# Back.net
KiCad netlist of a schematic drawn in Altium Designer
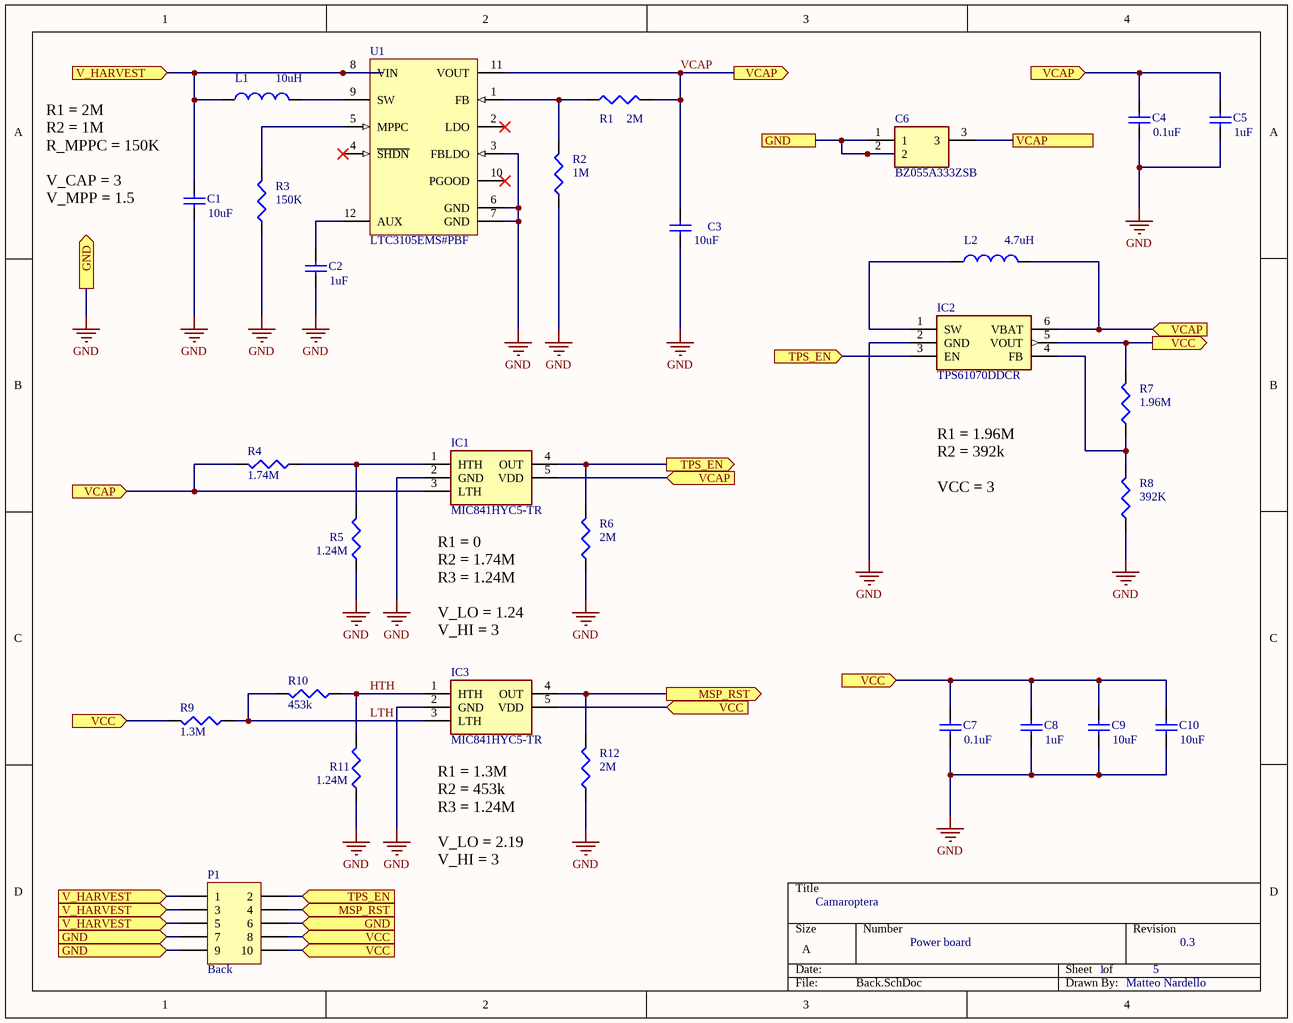
[diagram p0: Back.SchDoc]

(export (version "E")
  (design (tool "Eeschema 10.0.6"))
  (components
    (comp (ref "C1")
      (value "10uF")
      (footprint "1608[0603]")
      (description "CAP CER 6.3V X5R/X7R 0603")
      (fields (field (name "Comment") "Cap") (field (name "PUBLISHER") "Altium Limited"))
      (libsource (lib "Miscellaneous Devices") (part "Cap"))
    )
    (comp (ref "C2")
      (value "1uF")
      (footprint "1608[0603]")
      (description "CAP CER 6.3V X5R/X7R 0603")
      (fields (field (name "Comment") "Cap") (field (name "PUBLISHER") "Altium Limited"))
      (libsource (lib "Miscellaneous Devices") (part "Cap"))
    )
    (comp (ref "C3")
      (value "10uF")
      (footprint "1608[0603]")
      (description "CAP CER 6.3V X5R/X7R 0603")
      (fields (field (name "Comment") "Cap") (field (name "PUBLISHER") "Altium Limited"))
      (libsource (lib "Miscellaneous Devices") (part "Cap"))
    )
    (comp (ref "C4")
      (value "0.1uF")
      (footprint "1608[0603]")
      (description "CAP CER 6.3V X5R/X7R 0603")
      (fields (field (name "Comment") "Cap") (field (name "PUBLISHER") "Altium Limited"))
      (libsource (lib "Miscellaneous Devices") (part "Cap"))
    )
    (comp (ref "C5")
      (value "1uF")
      (footprint "1608[0603]")
      (description "CAP CER 6.3V X5R/X7R 0603")
      (fields (field (name "Comment") "Cap") (field (name "PUBLISHER") "Altium Limited"))
      (libsource (lib "Miscellaneous Devices") (part "Cap"))
    )
    (comp (ref "C6")
      (value "BZ055A333ZSB")
      (footprint "SamacSys:BZ054B223ZSB")
      (description "Capacitor")
      (fields
        (field (name "MANUFACTURER_PART_NUMBER") "BZ054B223ZSB")
        (field (name "MOUSER PART NUMBER") "581-BZ054B223ZSB")
      )
      (libsource (lib "SamacSys") (part "BZ054B223ZSB"))
    )
    (comp (ref "C7")
      (value "0.1uF")
      (footprint "1608[0603]")
      (description "CAP CER 6.3V X5R/X7R 0603")
      (fields (field (name "Comment") "Cap") (field (name "PUBLISHER") "Altium Limited"))
      (libsource (lib "Miscellaneous Devices") (part "Cap"))
    )
    (comp (ref "C8")
      (value "1uF")
      (footprint "1608[0603]")
      (description "CAP CER 6.3V X5R/X7R 0603")
      (fields (field (name "Comment") "Cap") (field (name "PUBLISHER") "Altium Limited"))
      (libsource (lib "Miscellaneous Devices") (part "Cap"))
    )
    (comp (ref "C9")
      (value "10uF")
      (footprint "1608[0603]")
      (description "CAP CER 6.3V X5R/X7R 0603")
      (fields (field (name "Comment") "Cap") (field (name "PUBLISHER") "Altium Limited"))
      (libsource (lib "Miscellaneous Devices") (part "Cap"))
    )
    (comp (ref "C10")
      (value "10uF")
      (footprint "1608[0603]")
      (description "CAP CER 6.3V X5R/X7R 0603")
      (fields (field (name "Comment") "Cap") (field (name "PUBLISHER") "Altium Limited"))
      (libsource (lib "Miscellaneous Devices") (part "Cap"))
    )
    (comp (ref "IC1")
      (value "MIC841HYC5-TR")
      (footprint "SamacSys:SOT65P210X110-5N")
      (description "Comparator with 1.25% Reference and Adjustable Hysteresis")
      (fields
        (field (name "MOUSER PART NUMBER") "998-MIC841HYC5TR")
        (field (name "RS PART NUMBER") "1654292")
      )
      (libsource (lib "*") (part "MIC841HYC5-TR"))
    )
    (comp (ref "IC2")
      (value "TPS61070DDCR")
      (footprint "SamacSys:SOT95P280X110-6N")
      (description "90% Efficient Synchronous Boost Converter With 600-mA Switch")
      (fields (field (name "MOUSER PART NUMBER") "595-TPS61070DDCR"))
      (libsource (lib "*") (part "TPS61070DDCR"))
    )
    (comp (ref "IC3")
      (value "MIC841HYC5-TR")
      (footprint "SamacSys:SOT65P210X110-5N")
      (description "Comparator with 1.25% Reference and Adjustable Hysteresis")
      (fields
        (field (name "MOUSER PART NUMBER") "998-MIC841HYC5TR")
        (field (name "RS PART NUMBER") "1654292")
      )
      (libsource (lib "*") (part "MIC841HYC5-TR"))
    )
    (comp (ref "L1")
      (value "10uH")
      (footprint "C1210")
      (description "Inductor")
      (fields (field (name "PART") "CBC3225T100KR") (field (name "PUBLISHER") "Altium Limited"))
      (libsource (lib "Miscellaneous Devices") (part "Inductor"))
    )
    (comp (ref "L2")
      (value "4.7uH")
      (footprint "C1210")
      (description "Inductor")
      (fields (field (name "PART") "CBC3225T4R7MR") (field (name "PUBLISHER") "Altium Limited"))
      (libsource (lib "Miscellaneous Devices") (part "Inductor"))
    )
    (comp (ref "P1")
      (value "Back")
      (footprint "FTE-105-03-X-DH")
      (description "Back board connector")
      (fields (field (name "PUBLISHER") "Altium Limited"))
      (libsource (lib "Miscellaneous Connectors") (part "Header 5X2"))
    )
    (comp (ref "R1")
      (value "2M")
      (footprint "1608[0603]")
      (description "RES 1/10W 1% 0603 SMD")
      (fields (field (name "Comment") "Res3") (field (name "PUBLISHER") "Altium Limited"))
      (libsource (lib "Miscellaneous Devices") (part "Res3"))
    )
    (comp (ref "R2")
      (value "1M")
      (footprint "1608[0603]")
      (description "RES 1/10W 1% 0603 SMD")
      (fields (field (name "Comment") "Res3") (field (name "PUBLISHER") "Altium Limited"))
      (libsource (lib "Miscellaneous Devices") (part "Res3"))
    )
    (comp (ref "R3")
      (value "150K")
      (footprint "1608[0603]")
      (description "RES 1/10W 1% 0603 SMD")
      (fields (field (name "Comment") "Res3") (field (name "PUBLISHER") "Altium Limited"))
      (libsource (lib "Miscellaneous Devices") (part "Res3"))
    )
    (comp (ref "R4")
      (value "1.74M")
      (footprint "1608[0603]")
      (description "RES 1/10W 1% 0603 SMD")
      (fields (field (name "Comment") "Res3") (field (name "PUBLISHER") "Altium Limited"))
      (libsource (lib "Miscellaneous Devices") (part "Res3"))
    )
    (comp (ref "R5")
      (value "1.24M")
      (footprint "1608[0603]")
      (description "RES 1/10W 1% 0603 SMD")
      (fields (field (name "Comment") "Res3") (field (name "PUBLISHER") "Altium Limited"))
      (libsource (lib "Miscellaneous Devices") (part "Res3"))
    )
    (comp (ref "R6")
      (value "2M")
      (footprint "1608[0603]")
      (description "RES 1/10W 1% 0603 SMD")
      (fields (field (name "Comment") "Res3") (field (name "PUBLISHER") "Altium Limited"))
      (libsource (lib "Miscellaneous Devices") (part "Res3"))
    )
    (comp (ref "R7")
      (value "1.96M")
      (footprint "1608[0603]")
      (description "RES 1/10W 1% 0603 SMD")
      (fields (field (name "Comment") "Res3") (field (name "PUBLISHER") "Altium Limited"))
      (libsource (lib "Miscellaneous Devices") (part "Res3"))
    )
    (comp (ref "R8")
      (value "392K")
      (footprint "1608[0603]")
      (description "RES 1/10W 1% 0603 SMD")
      (fields (field (name "Comment") "Res3") (field (name "PUBLISHER") "Altium Limited"))
      (libsource (lib "Miscellaneous Devices") (part "Res3"))
    )
    (comp (ref "R9")
      (value "1.3M")
      (footprint "1608[0603]")
      (description "RES 1/10W 1% 0603 SMD")
      (fields (field (name "Comment") "Res3") (field (name "PUBLISHER") "Altium Limited"))
      (libsource (lib "Miscellaneous Devices") (part "Res3"))
    )
    (comp (ref "R10")
      (value "453k")
      (footprint "1608[0603]")
      (description "RES 1/10W 1% 0603 SMD")
      (fields (field (name "Comment") "Res3") (field (name "PUBLISHER") "Altium Limited"))
      (libsource (lib "Miscellaneous Devices") (part "Res3"))
    )
    (comp (ref "R11")
      (value "1.24M")
      (footprint "1608[0603]")
      (description "RES 1/10W 1% 0603 SMD")
      (fields (field (name "Comment") "Res3") (field (name "PUBLISHER") "Altium Limited"))
      (libsource (lib "Miscellaneous Devices") (part "Res3"))
    )
    (comp (ref "R12")
      (value "2M")
      (footprint "1608[0603]")
      (description "RES 1/10W 1% 0603 SMD")
      (fields (field (name "Comment") "Res3") (field (name "PUBLISHER") "Altium Limited"))
      (libsource (lib "Miscellaneous Devices") (part "Res3"))
    )
    (comp (ref "U1")
      (value "LTC3105EMS#PBF")
      (footprint "LT-MS-12_N")
      (fields (field (name "MANUFACTURER") "Linear Technology"))
      (libsource (lib "Altium Content Vault") (part "LT-LTC3105-MS-12"))
    )
  )
  (nets
    (net (code "1") (name "/HTH") (class "Default")
      (node (ref "IC3") (pin "1") (pinfunction "HTH_1") (pintype "passive"))
      (node (ref "R10") (pin "1") (pinfunction "1_1") (pintype "passive"))
      (node (ref "R11") (pin "2") (pinfunction "2_2") (pintype "passive"))
    )
    (net (code "2") (name "/LTH") (class "Default")
      (node (ref "IC3") (pin "3") (pinfunction "LTH_3") (pintype "passive"))
      (node (ref "R10") (pin "2") (pinfunction "2_2") (pintype "passive"))
      (node (ref "R9") (pin "1") (pinfunction "1_1") (pintype "passive"))
    )
    (net (code "3") (name "/MSP_RST") (class "Default")
      (node (ref "IC3") (pin "4") (pinfunction "OUT_4") (pintype "passive"))
      (node (ref "P1") (pin "4") (pinfunction "4_4") (pintype "passive"))
      (node (ref "R12") (pin "2") (pinfunction "2_2") (pintype "passive"))
    )
    (net (code "4") (name "/TPS_EN") (class "Default")
      (node (ref "IC1") (pin "4") (pinfunction "OUT_4") (pintype "passive"))
      (node (ref "IC2") (pin "3") (pinfunction "EN_3") (pintype "passive"))
      (node (ref "P1") (pin "2") (pinfunction "2_2") (pintype "passive"))
      (node (ref "R6") (pin "2") (pinfunction "2_2") (pintype "passive"))
    )
    (net (code "5") (name "/VCAP") (class "Default")
      (node (ref "C3") (pin "2") (pinfunction "2_2") (pintype "passive"))
      (node (ref "C4") (pin "2") (pinfunction "2_2") (pintype "passive"))
      (node (ref "C5") (pin "2") (pinfunction "2_2") (pintype "passive"))
      (node (ref "C6") (pin "3") (pinfunction "3_3") (pintype "passive"))
      (node (ref "IC1") (pin "3") (pinfunction "LTH_3") (pintype "passive"))
      (node (ref "IC1") (pin "5") (pinfunction "VDD_5") (pintype "passive"))
      (node (ref "IC2") (pin "6") (pinfunction "VBAT_6") (pintype "passive"))
      (node (ref "L2") (pin "2") (pinfunction "2_2") (pintype "passive"))
      (node (ref "R1") (pin "2") (pinfunction "2_2") (pintype "passive"))
      (node (ref "R4") (pin "2") (pinfunction "2_2") (pintype "passive"))
      (node (ref "U1") (pin "11") (pinfunction "VOUT_11") (pintype "power_in"))
    )
    (net (code "6") (name "/VCC") (class "Default")
      (node (ref "C10") (pin "2") (pinfunction "2_2") (pintype "passive"))
      (node (ref "C7") (pin "2") (pinfunction "2_2") (pintype "passive"))
      (node (ref "C8") (pin "2") (pinfunction "2_2") (pintype "passive"))
      (node (ref "C9") (pin "2") (pinfunction "2_2") (pintype "passive"))
      (node (ref "IC2") (pin "5") (pinfunction "VOUT_5") (pintype "output"))
      (node (ref "IC3") (pin "5") (pinfunction "VDD_5") (pintype "passive"))
      (node (ref "P1") (pin "10") (pinfunction "10_10") (pintype "passive"))
      (node (ref "P1") (pin "8") (pinfunction "8_8") (pintype "passive"))
      (node (ref "R7") (pin "2") (pinfunction "2_2") (pintype "passive"))
      (node (ref "R9") (pin "2") (pinfunction "2_2") (pintype "passive"))
    )
    (net (code "7") (name "/V_HARVEST") (class "Default")
      (node (ref "C1") (pin "2") (pinfunction "2_2") (pintype "passive"))
      (node (ref "L1") (pin "1") (pinfunction "1_1") (pintype "passive"))
      (node (ref "P1") (pin "1") (pinfunction "1_1") (pintype "passive"))
      (node (ref "P1") (pin "3") (pinfunction "3_3") (pintype "passive"))
      (node (ref "P1") (pin "5") (pinfunction "5_5") (pintype "passive"))
      (node (ref "U1") (pin "8") (pinfunction "VIN_8") (pintype "power_in"))
    )
    (net (code "8") (name "GND") (class "Default")
      (node (ref "C1") (pin "1") (pinfunction "1_1") (pintype "passive"))
      (node (ref "C10") (pin "1") (pinfunction "1_1") (pintype "passive"))
      (node (ref "C2") (pin "1") (pinfunction "1_1") (pintype "passive"))
      (node (ref "C3") (pin "1") (pinfunction "1_1") (pintype "passive"))
      (node (ref "C4") (pin "1") (pinfunction "1_1") (pintype "passive"))
      (node (ref "C5") (pin "1") (pinfunction "1_1") (pintype "passive"))
      (node (ref "C6") (pin "1") (pinfunction "1_1") (pintype "passive"))
      (node (ref "C6") (pin "2") (pinfunction "2_2") (pintype "passive"))
      (node (ref "C7") (pin "1") (pinfunction "1_1") (pintype "passive"))
      (node (ref "C8") (pin "1") (pinfunction "1_1") (pintype "passive"))
      (node (ref "C9") (pin "1") (pinfunction "1_1") (pintype "passive"))
      (node (ref "IC1") (pin "2") (pinfunction "GND_2") (pintype "passive"))
      (node (ref "IC2") (pin "2") (pinfunction "GND_2") (pintype "power_in"))
      (node (ref "IC3") (pin "2") (pinfunction "GND_2") (pintype "passive"))
      (node (ref "P1") (pin "6") (pinfunction "6_6") (pintype "passive"))
      (node (ref "P1") (pin "7") (pinfunction "7_7") (pintype "passive"))
      (node (ref "P1") (pin "9") (pinfunction "9_9") (pintype "passive"))
      (node (ref "R11") (pin "1") (pinfunction "1_1") (pintype "passive"))
      (node (ref "R12") (pin "1") (pinfunction "1_1") (pintype "passive"))
      (node (ref "R2") (pin "1") (pinfunction "1_1") (pintype "passive"))
      (node (ref "R3") (pin "1") (pinfunction "1_1") (pintype "passive"))
      (node (ref "R5") (pin "1") (pinfunction "1_1") (pintype "passive"))
      (node (ref "R6") (pin "1") (pinfunction "1_1") (pintype "passive"))
      (node (ref "R8") (pin "1") (pinfunction "1_1") (pintype "passive"))
      (node (ref "U1") (pin "3") (pinfunction "FBLDO_3") (pintype "input"))
      (node (ref "U1") (pin "6") (pinfunction "GND_6") (pintype "power_in"))
      (node (ref "U1") (pin "7") (pinfunction "GND_7") (pintype "power_in"))
    )
    (net (code "9") (name "Net-(IC1-HTH)") (class "Default")
      (node (ref "IC1") (pin "1") (pinfunction "HTH_1") (pintype "passive"))
      (node (ref "R4") (pin "1") (pinfunction "1_1") (pintype "passive"))
      (node (ref "R5") (pin "2") (pinfunction "2_2") (pintype "passive"))
    )
    (net (code "10") (name "Net-(IC2-FB)") (class "Default")
      (node (ref "IC2") (pin "4") (pinfunction "FB_4") (pintype "passive"))
      (node (ref "R7") (pin "1") (pinfunction "1_1") (pintype "passive"))
      (node (ref "R8") (pin "2") (pinfunction "2_2") (pintype "passive"))
    )
    (net (code "11") (name "Net-(IC2-SW)") (class "Default")
      (node (ref "IC2") (pin "1") (pinfunction "SW_1") (pintype "passive"))
      (node (ref "L2") (pin "1") (pinfunction "1_1") (pintype "passive"))
    )
    (net (code "12") (name "Net-(U1-AUX)") (class "Default")
      (node (ref "C2") (pin "2") (pinfunction "2_2") (pintype "passive"))
      (node (ref "U1") (pin "12") (pinfunction "AUX_12") (pintype "power_in"))
    )
    (net (code "13") (name "Net-(U1-FB)") (class "Default")
      (node (ref "R1") (pin "1") (pinfunction "1_1") (pintype "passive"))
      (node (ref "R2") (pin "2") (pinfunction "2_2") (pintype "passive"))
      (node (ref "U1") (pin "1") (pinfunction "FB_1") (pintype "input"))
    )
    (net (code "14") (name "Net-(U1-MPPC)") (class "Default")
      (node (ref "R3") (pin "2") (pinfunction "2_2") (pintype "passive"))
      (node (ref "U1") (pin "5") (pinfunction "MPPC_5") (pintype "input"))
    )
    (net (code "15") (name "Net-(U1-SW)") (class "Default")
      (node (ref "L1") (pin "2") (pinfunction "2_2") (pintype "passive"))
      (node (ref "U1") (pin "9") (pinfunction "SW_9") (pintype "power_in"))
    )
    (net (code "16") (name "unconnected-(U1-LDO-Pad2)") (class "Default")
      (node (ref "U1") (pin "2") (pinfunction "LDO_2") (pintype "power_in+no_connect"))
    )
    (net (code "17") (name "unconnected-(U1-PGOOD-Pad10)") (class "Default")
      (node (ref "U1") (pin "10") (pinfunction "PGOOD_10") (pintype "open_collector+no_connect"))
    )
    (net (code "18") (name "unconnected-(U1-~{SHDN}-Pad4)") (class "Default")
      (node (ref "U1") (pin "4") (pinfunction "~{SHDN}_4") (pintype "input+no_connect"))
    )
  )
)
